# out8-V2_1.net
KiCad netlist of a schematic drawn in EAGLE
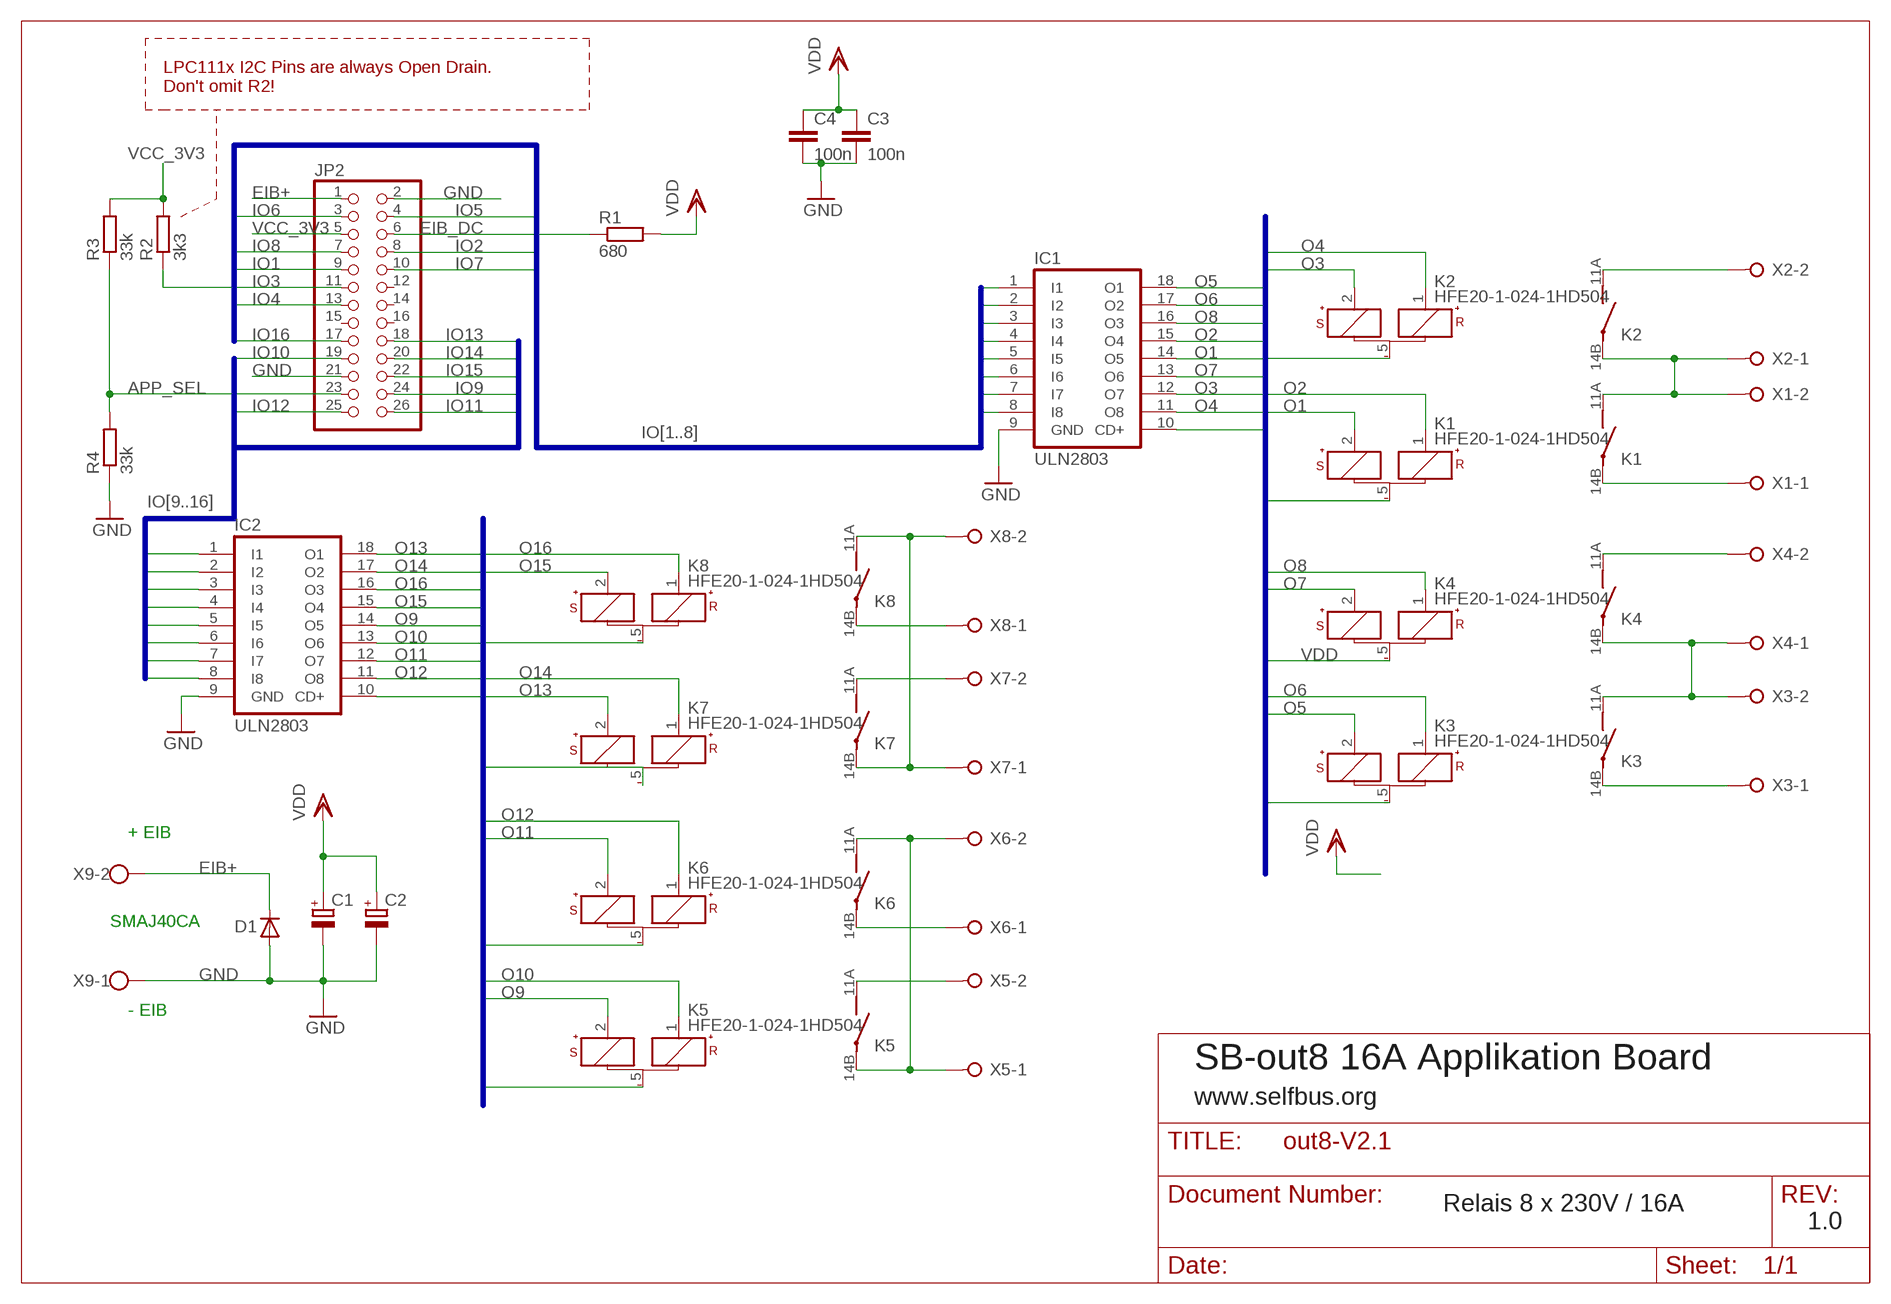
[diagram p0: schematic, sheet 1]

(export (version "E")
  (design (tool "Eeschema 10.0.6"))
  (components
    (comp (ref "C1")
      (value "CPOL-EUE3.5-8")
      (footprint "eagle-import:E3,5-8")
      (libsource (lib "eagle-import") (part "CPOL-EUE3.5-8"))
    )
    (comp (ref "C2")
      (value "CPOL-EUE3.5-8")
      (footprint "eagle-import:E3,5-8")
      (libsource (lib "eagle-import") (part "CPOL-EUE3.5-8"))
    )
    (comp (ref "C3")
      (value "100n")
      (footprint "eagle-import:C1206")
      (libsource (lib "eagle-import") (part "C-EUC1206"))
    )
    (comp (ref "C4")
      (value "100n")
      (footprint "eagle-import:C1206")
      (libsource (lib "eagle-import") (part "C-EUC1206"))
    )
    (comp (ref "D1")
      (value "D-SMB")
      (footprint "eagle-import:SMB")
      (libsource (lib "eagle-import") (part "D-SMB"))
    )
    (comp (ref "IC1")
      (value "ULN2803")
      (footprint "eagle-import:SO18W")
      (libsource (lib "eagle-import") (part "ULN2803ASOP18"))
    )
    (comp (ref "IC2")
      (value "ULN2803")
      (footprint "eagle-import:SO18W")
      (libsource (lib "eagle-import") (part "ULN2803ASOP18"))
    )
    (comp (ref "JP2")
      (value "PINHD-2X13_2.54-SMD")
      (footprint "eagle-import:2X13SMD")
      (libsource (lib "eagle-import") (part "PINHD-2X13_2.54-SMD"))
    )
    (comp (ref "K1")
      (value "HFE20-1-024-1HD504")
      (footprint "eagle-import:HFE20-3-504")
      (libsource (lib "eagle-import") (part "HFE20-1-024-1HD504"))
    )
    (comp (ref "K2")
      (value "HFE20-1-024-1HD504")
      (footprint "eagle-import:HFE20-3-504")
      (libsource (lib "eagle-import") (part "HFE20-1-024-1HD504"))
    )
    (comp (ref "K3")
      (value "HFE20-1-024-1HD504")
      (footprint "eagle-import:HFE20-3-504")
      (libsource (lib "eagle-import") (part "HFE20-1-024-1HD504"))
    )
    (comp (ref "K4")
      (value "HFE20-1-024-1HD504")
      (footprint "eagle-import:HFE20-3-504")
      (libsource (lib "eagle-import") (part "HFE20-1-024-1HD504"))
    )
    (comp (ref "K5")
      (value "HFE20-1-024-1HD504")
      (footprint "eagle-import:HFE20-3-504")
      (libsource (lib "eagle-import") (part "HFE20-1-024-1HD504"))
    )
    (comp (ref "K6")
      (value "HFE20-1-024-1HD504")
      (footprint "eagle-import:HFE20-3-504")
      (libsource (lib "eagle-import") (part "HFE20-1-024-1HD504"))
    )
    (comp (ref "K7")
      (value "HFE20-1-024-1HD504")
      (footprint "eagle-import:HFE20-3-504")
      (libsource (lib "eagle-import") (part "HFE20-1-024-1HD504"))
    )
    (comp (ref "K8")
      (value "HFE20-1-024-1HD504")
      (footprint "eagle-import:HFE20-3-504")
      (libsource (lib "eagle-import") (part "HFE20-1-024-1HD504"))
    )
    (comp (ref "R1")
      (value "680")
      (footprint "eagle-import:M1206")
      (libsource (lib "eagle-import") (part "R-EU_M1206"))
    )
    (comp (ref "R2")
      (value "3k3")
      (footprint "eagle-import:M1206")
      (libsource (lib "eagle-import") (part "R-EU_M1206"))
    )
    (comp (ref "R3")
      (value "33k")
      (footprint "eagle-import:M1206")
      (libsource (lib "eagle-import") (part "R-EU_M1206"))
    )
    (comp (ref "R4")
      (value "33k")
      (footprint "eagle-import:M1206")
      (libsource (lib "eagle-import") (part "R-EU_M1206"))
    )
    (comp (ref "X1")
      (value "W237-02P")
      (footprint "eagle-import:W237-132")
      (libsource (lib "eagle-import") (part "W237-02P"))
    )
    (comp (ref "X2")
      (value "W237-02P")
      (footprint "eagle-import:W237-132")
      (libsource (lib "eagle-import") (part "W237-02P"))
    )
    (comp (ref "X3")
      (value "W237-02P")
      (footprint "eagle-import:W237-132")
      (libsource (lib "eagle-import") (part "W237-02P"))
    )
    (comp (ref "X4")
      (value "W237-02P")
      (footprint "eagle-import:W237-132")
      (libsource (lib "eagle-import") (part "W237-02P"))
    )
    (comp (ref "X5")
      (value "W237-02P")
      (footprint "eagle-import:W237-132")
      (libsource (lib "eagle-import") (part "W237-02P"))
    )
    (comp (ref "X6")
      (value "W237-02P")
      (footprint "eagle-import:W237-132")
      (libsource (lib "eagle-import") (part "W237-02P"))
    )
    (comp (ref "X7")
      (value "W237-02P")
      (footprint "eagle-import:W237-132")
      (libsource (lib "eagle-import") (part "W237-02P"))
    )
    (comp (ref "X8")
      (value "W237-02P")
      (footprint "eagle-import:W237-132")
      (libsource (lib "eagle-import") (part "W237-02P"))
    )
    (comp (ref "X9")
      (value "W237-102")
      (footprint "eagle-import:W237-102")
      (libsource (lib "eagle-import") (part "W237-102"))
    )
  )
  (nets
    (net (code "1") (name "/APP_SEL") (class "Default")
      (node (ref "JP2") (pin "23") (pinfunction "23_23") (pintype "passive"))
      (node (ref "R3") (pin "1") (pinfunction "1_1") (pintype "passive"))
      (node (ref "R4") (pin "2") (pinfunction "2_2") (pintype "passive"))
    )
    (net (code "2") (name "/EIB+") (class "Default")
      (node (ref "D1") (pin "1") (pinfunction "C_1") (pintype "passive"))
      (node (ref "JP2") (pin "1") (pinfunction "1_1") (pintype "passive"))
      (node (ref "X9") (pin "2") (pinfunction "KL_2") (pintype "passive"))
    )
    (net (code "3") (name "/EIB_DC") (class "Default")
      (node (ref "JP2") (pin "6") (pinfunction "6_6") (pintype "passive"))
      (node (ref "R1") (pin "1") (pinfunction "1_1") (pintype "passive"))
    )
    (net (code "4") (name "/IO1") (class "Default")
      (node (ref "IC1") (pin "5") (pinfunction "I5_5") (pintype "input"))
      (node (ref "JP2") (pin "9") (pinfunction "9_9") (pintype "passive"))
    )
    (net (code "5") (name "/IO2") (class "Default")
      (node (ref "IC1") (pin "4") (pinfunction "I4_4") (pintype "input"))
      (node (ref "JP2") (pin "8") (pinfunction "8_8") (pintype "passive"))
    )
    (net (code "6") (name "/IO3") (class "Default")
      (node (ref "IC1") (pin "7") (pinfunction "I7_7") (pintype "input"))
      (node (ref "JP2") (pin "11") (pinfunction "11_11") (pintype "passive"))
      (node (ref "R2") (pin "1") (pinfunction "1_1") (pintype "passive"))
    )
    (net (code "7") (name "/IO4") (class "Default")
      (node (ref "IC1") (pin "8") (pinfunction "I8_8") (pintype "input"))
      (node (ref "JP2") (pin "13") (pinfunction "13_13") (pintype "passive"))
    )
    (net (code "8") (name "/IO5") (class "Default")
      (node (ref "IC1") (pin "1") (pinfunction "I1_1") (pintype "input"))
      (node (ref "JP2") (pin "4") (pinfunction "4_4") (pintype "passive"))
    )
    (net (code "9") (name "/IO6") (class "Default")
      (node (ref "IC1") (pin "2") (pinfunction "I2_2") (pintype "input"))
      (node (ref "JP2") (pin "3") (pinfunction "3_3") (pintype "passive"))
    )
    (net (code "10") (name "/IO7") (class "Default")
      (node (ref "IC1") (pin "6") (pinfunction "I6_6") (pintype "input"))
      (node (ref "JP2") (pin "10") (pinfunction "10_10") (pintype "passive"))
    )
    (net (code "11") (name "/IO8") (class "Default")
      (node (ref "IC1") (pin "3") (pinfunction "I3_3") (pintype "input"))
      (node (ref "JP2") (pin "7") (pinfunction "7_7") (pintype "passive"))
    )
    (net (code "12") (name "/IO9") (class "Default")
      (node (ref "IC2") (pin "5") (pinfunction "I5_5") (pintype "input"))
      (node (ref "JP2") (pin "24") (pinfunction "24_24") (pintype "passive"))
    )
    (net (code "13") (name "/IO10") (class "Default")
      (node (ref "IC2") (pin "6") (pinfunction "I6_6") (pintype "input"))
      (node (ref "JP2") (pin "19") (pinfunction "19_19") (pintype "passive"))
    )
    (net (code "14") (name "/IO11") (class "Default")
      (node (ref "IC2") (pin "7") (pinfunction "I7_7") (pintype "input"))
      (node (ref "JP2") (pin "26") (pinfunction "26_26") (pintype "passive"))
    )
    (net (code "15") (name "/IO12") (class "Default")
      (node (ref "IC2") (pin "8") (pinfunction "I8_8") (pintype "input"))
      (node (ref "JP2") (pin "25") (pinfunction "25_25") (pintype "passive"))
    )
    (net (code "16") (name "/IO13") (class "Default")
      (node (ref "IC2") (pin "1") (pinfunction "I1_1") (pintype "input"))
      (node (ref "JP2") (pin "18") (pinfunction "18_18") (pintype "passive"))
    )
    (net (code "17") (name "/IO14") (class "Default")
      (node (ref "IC2") (pin "2") (pinfunction "I2_2") (pintype "input"))
      (node (ref "JP2") (pin "20") (pinfunction "20_20") (pintype "passive"))
    )
    (net (code "18") (name "/IO15") (class "Default")
      (node (ref "IC2") (pin "4") (pinfunction "I4_4") (pintype "input"))
      (node (ref "JP2") (pin "22") (pinfunction "22_22") (pintype "passive"))
    )
    (net (code "19") (name "/IO16") (class "Default")
      (node (ref "IC2") (pin "3") (pinfunction "I3_3") (pintype "input"))
      (node (ref "JP2") (pin "17") (pinfunction "17_17") (pintype "passive"))
    )
    (net (code "22") (name "/O1") (class "Default")
      (node (ref "IC1") (pin "14") (pinfunction "O5_14") (pintype "open_collector"))
      (node (ref "K1") (pin "2") (pinfunction "S+_2") (pintype "passive"))
    )
    (net (code "23") (name "/O2") (class "Default")
      (node (ref "IC1") (pin "15") (pinfunction "O4_15") (pintype "open_collector"))
      (node (ref "K1") (pin "1") (pinfunction "R+_1") (pintype "passive"))
    )
    (net (code "24") (name "/O3") (class "Default")
      (node (ref "IC1") (pin "12") (pinfunction "O7_12") (pintype "open_collector"))
      (node (ref "K2") (pin "2") (pinfunction "S+_2") (pintype "passive"))
    )
    (net (code "25") (name "/O4") (class "Default")
      (node (ref "IC1") (pin "11") (pinfunction "O8_11") (pintype "open_collector"))
      (node (ref "K2") (pin "1") (pinfunction "R+_1") (pintype "passive"))
    )
    (net (code "26") (name "/O5") (class "Default")
      (node (ref "IC1") (pin "18") (pinfunction "O1_18") (pintype "open_collector"))
      (node (ref "K3") (pin "2") (pinfunction "S+_2") (pintype "passive"))
    )
    (net (code "27") (name "/O6") (class "Default")
      (node (ref "IC1") (pin "17") (pinfunction "O2_17") (pintype "open_collector"))
      (node (ref "K3") (pin "1") (pinfunction "R+_1") (pintype "passive"))
    )
    (net (code "28") (name "/O7") (class "Default")
      (node (ref "IC1") (pin "13") (pinfunction "O6_13") (pintype "open_collector"))
      (node (ref "K4") (pin "2") (pinfunction "S+_2") (pintype "passive"))
    )
    (net (code "29") (name "/O8") (class "Default")
      (node (ref "IC1") (pin "16") (pinfunction "O3_16") (pintype "open_collector"))
      (node (ref "K4") (pin "1") (pinfunction "R+_1") (pintype "passive"))
    )
    (net (code "30") (name "/O9") (class "Default")
      (node (ref "IC2") (pin "14") (pinfunction "O5_14") (pintype "open_collector"))
      (node (ref "K5") (pin "2") (pinfunction "S+_2") (pintype "passive"))
    )
    (net (code "31") (name "/O10") (class "Default")
      (node (ref "IC2") (pin "13") (pinfunction "O6_13") (pintype "open_collector"))
      (node (ref "K5") (pin "1") (pinfunction "R+_1") (pintype "passive"))
    )
    (net (code "32") (name "/O11") (class "Default")
      (node (ref "IC2") (pin "12") (pinfunction "O7_12") (pintype "open_collector"))
      (node (ref "K6") (pin "2") (pinfunction "S+_2") (pintype "passive"))
    )
    (net (code "33") (name "/O12") (class "Default")
      (node (ref "IC2") (pin "11") (pinfunction "O8_11") (pintype "open_collector"))
      (node (ref "K6") (pin "1") (pinfunction "R+_1") (pintype "passive"))
    )
    (net (code "34") (name "/O13") (class "Default")
      (node (ref "IC2") (pin "18") (pinfunction "O1_18") (pintype "open_collector"))
      (node (ref "K7") (pin "2") (pinfunction "S+_2") (pintype "passive"))
    )
    (net (code "35") (name "/O14") (class "Default")
      (node (ref "IC2") (pin "17") (pinfunction "O2_17") (pintype "open_collector"))
      (node (ref "K7") (pin "1") (pinfunction "R+_1") (pintype "passive"))
    )
    (net (code "36") (name "/O15") (class "Default")
      (node (ref "IC2") (pin "15") (pinfunction "O4_15") (pintype "open_collector"))
      (node (ref "K8") (pin "2") (pinfunction "S+_2") (pintype "passive"))
    )
    (net (code "37") (name "/O16") (class "Default")
      (node (ref "IC2") (pin "16") (pinfunction "O3_16") (pintype "open_collector"))
      (node (ref "K8") (pin "1") (pinfunction "R+_1") (pintype "passive"))
    )
    (net (code "38") (name "/VCC_3V3") (class "Default")
      (node (ref "JP2") (pin "5") (pinfunction "5_5") (pintype "passive"))
      (node (ref "R2") (pin "2") (pinfunction "2_2") (pintype "passive"))
      (node (ref "R3") (pin "2") (pinfunction "2_2") (pintype "passive"))
    )
    (net (code "39") (name "GND") (class "Default")
      (node (ref "C1") (pin "-") (pinfunction "-_-") (pintype "passive"))
      (node (ref "C2") (pin "-") (pinfunction "-_-") (pintype "passive"))
      (node (ref "C3") (pin "2") (pinfunction "2_2") (pintype "passive"))
      (node (ref "C4") (pin "2") (pinfunction "2_2") (pintype "passive"))
      (node (ref "D1") (pin "2") (pinfunction "A_2") (pintype "passive"))
      (node (ref "IC1") (pin "9") (pinfunction "GND_9") (pintype "power_in"))
      (node (ref "IC2") (pin "9") (pinfunction "GND_9") (pintype "power_in"))
      (node (ref "JP2") (pin "2") (pinfunction "2_2") (pintype "passive"))
      (node (ref "JP2") (pin "21") (pinfunction "21_21") (pintype "passive"))
      (node (ref "R4") (pin "1") (pinfunction "1_1") (pintype "passive"))
      (node (ref "X9") (pin "1") (pinfunction "KL_1") (pintype "passive"))
    )
    (net (code "40") (name "Net-(K1B-PA)") (class "Default")
      (node (ref "K1") (pin "14B") (pinfunction "PA_14B") (pintype "passive"))
      (node (ref "X1") (pin "1") (pinfunction "KL_1") (pintype "passive"))
    )
    (net (code "41") (name "Net-(K1B-PB)") (class "Default")
      (node (ref "K1") (pin "11A") (pinfunction "PB_11A") (pintype "passive"))
      (node (ref "K2") (pin "14B") (pinfunction "PA_14B") (pintype "passive"))
      (node (ref "X1") (pin "2") (pinfunction "KL_2") (pintype "passive"))
      (node (ref "X2") (pin "1") (pinfunction "KL_1") (pintype "passive"))
    )
    (net (code "42") (name "Net-(K2B-PB)") (class "Default")
      (node (ref "K2") (pin "11A") (pinfunction "PB_11A") (pintype "passive"))
      (node (ref "X2") (pin "2") (pinfunction "KL_2") (pintype "passive"))
    )
    (net (code "43") (name "Net-(K3B-PA)") (class "Default")
      (node (ref "K3") (pin "14B") (pinfunction "PA_14B") (pintype "passive"))
      (node (ref "X3") (pin "1") (pinfunction "KL_1") (pintype "passive"))
    )
    (net (code "44") (name "Net-(K3B-PB)") (class "Default")
      (node (ref "K3") (pin "11A") (pinfunction "PB_11A") (pintype "passive"))
      (node (ref "K4") (pin "14B") (pinfunction "PA_14B") (pintype "passive"))
      (node (ref "X3") (pin "2") (pinfunction "KL_2") (pintype "passive"))
      (node (ref "X4") (pin "1") (pinfunction "KL_1") (pintype "passive"))
    )
    (net (code "45") (name "Net-(K4B-PB)") (class "Default")
      (node (ref "K4") (pin "11A") (pinfunction "PB_11A") (pintype "passive"))
      (node (ref "X4") (pin "2") (pinfunction "KL_2") (pintype "passive"))
    )
    (net (code "46") (name "Net-(K5B-PA)") (class "Default")
      (node (ref "K5") (pin "14B") (pinfunction "PA_14B") (pintype "passive"))
      (node (ref "K6") (pin "11A") (pinfunction "PB_11A") (pintype "passive"))
      (node (ref "X5") (pin "1") (pinfunction "KL_1") (pintype "passive"))
      (node (ref "X6") (pin "2") (pinfunction "KL_2") (pintype "passive"))
    )
    (net (code "47") (name "Net-(K5B-PB)") (class "Default")
      (node (ref "K5") (pin "11A") (pinfunction "PB_11A") (pintype "passive"))
      (node (ref "X5") (pin "2") (pinfunction "KL_2") (pintype "passive"))
    )
    (net (code "48") (name "Net-(K6B-PA)") (class "Default")
      (node (ref "K6") (pin "14B") (pinfunction "PA_14B") (pintype "passive"))
      (node (ref "X6") (pin "1") (pinfunction "KL_1") (pintype "passive"))
    )
    (net (code "49") (name "Net-(K7B-PA)") (class "Default")
      (node (ref "K7") (pin "14B") (pinfunction "PA_14B") (pintype "passive"))
      (node (ref "K8") (pin "11A") (pinfunction "PB_11A") (pintype "passive"))
      (node (ref "X7") (pin "1") (pinfunction "KL_1") (pintype "passive"))
      (node (ref "X8") (pin "2") (pinfunction "KL_2") (pintype "passive"))
    )
    (net (code "50") (name "Net-(K7B-PB)") (class "Default")
      (node (ref "K7") (pin "11A") (pinfunction "PB_11A") (pintype "passive"))
      (node (ref "X7") (pin "2") (pinfunction "KL_2") (pintype "passive"))
    )
    (net (code "51") (name "Net-(K8B-PA)") (class "Default")
      (node (ref "K8") (pin "14B") (pinfunction "PA_14B") (pintype "passive"))
      (node (ref "X8") (pin "1") (pinfunction "KL_1") (pintype "passive"))
    )
    (net (code "52") (name "VDD") (class "Default")
      (node (ref "C1") (pin "+") (pinfunction "+_+") (pintype "passive"))
      (node (ref "C2") (pin "+") (pinfunction "+_+") (pintype "passive"))
      (node (ref "C3") (pin "1") (pinfunction "1_1") (pintype "passive"))
      (node (ref "C4") (pin "1") (pinfunction "1_1") (pintype "passive"))
      (node (ref "IC1") (pin "10") (pinfunction "CD+_10") (pintype "passive"))
      (node (ref "IC2") (pin "10") (pinfunction "CD+_10") (pintype "passive"))
      (node (ref "K1") (pin "5") (pinfunction "-_5") (pintype "passive"))
      (node (ref "K2") (pin "5") (pinfunction "-_5") (pintype "passive"))
      (node (ref "K3") (pin "5") (pinfunction "-_5") (pintype "passive"))
      (node (ref "K4") (pin "5") (pinfunction "-_5") (pintype "passive"))
      (node (ref "K5") (pin "5") (pinfunction "-_5") (pintype "passive"))
      (node (ref "K6") (pin "5") (pinfunction "-_5") (pintype "passive"))
      (node (ref "K7") (pin "5") (pinfunction "-_5") (pintype "passive"))
      (node (ref "K8") (pin "5") (pinfunction "-_5") (pintype "passive"))
      (node (ref "R1") (pin "2") (pinfunction "2_2") (pintype "passive"))
    )
    (net (code "53") (name "unconnected-(JP2-Pad12)") (class "Default")
      (node (ref "JP2") (pin "12") (pinfunction "12_12") (pintype "passive"))
    )
    (net (code "54") (name "unconnected-(JP2-Pad14)") (class "Default")
      (node (ref "JP2") (pin "14") (pinfunction "14_14") (pintype "passive"))
    )
    (net (code "55") (name "unconnected-(JP2-Pad15)") (class "Default")
      (node (ref "JP2") (pin "15") (pinfunction "15_15") (pintype "passive"))
    )
    (net (code "56") (name "unconnected-(JP2-Pad16)") (class "Default")
      (node (ref "JP2") (pin "16") (pinfunction "16_16") (pintype "passive"))
    )
  )
)
